# Sheet1.net
KiCad netlist of a schematic drawn in Altium Designer
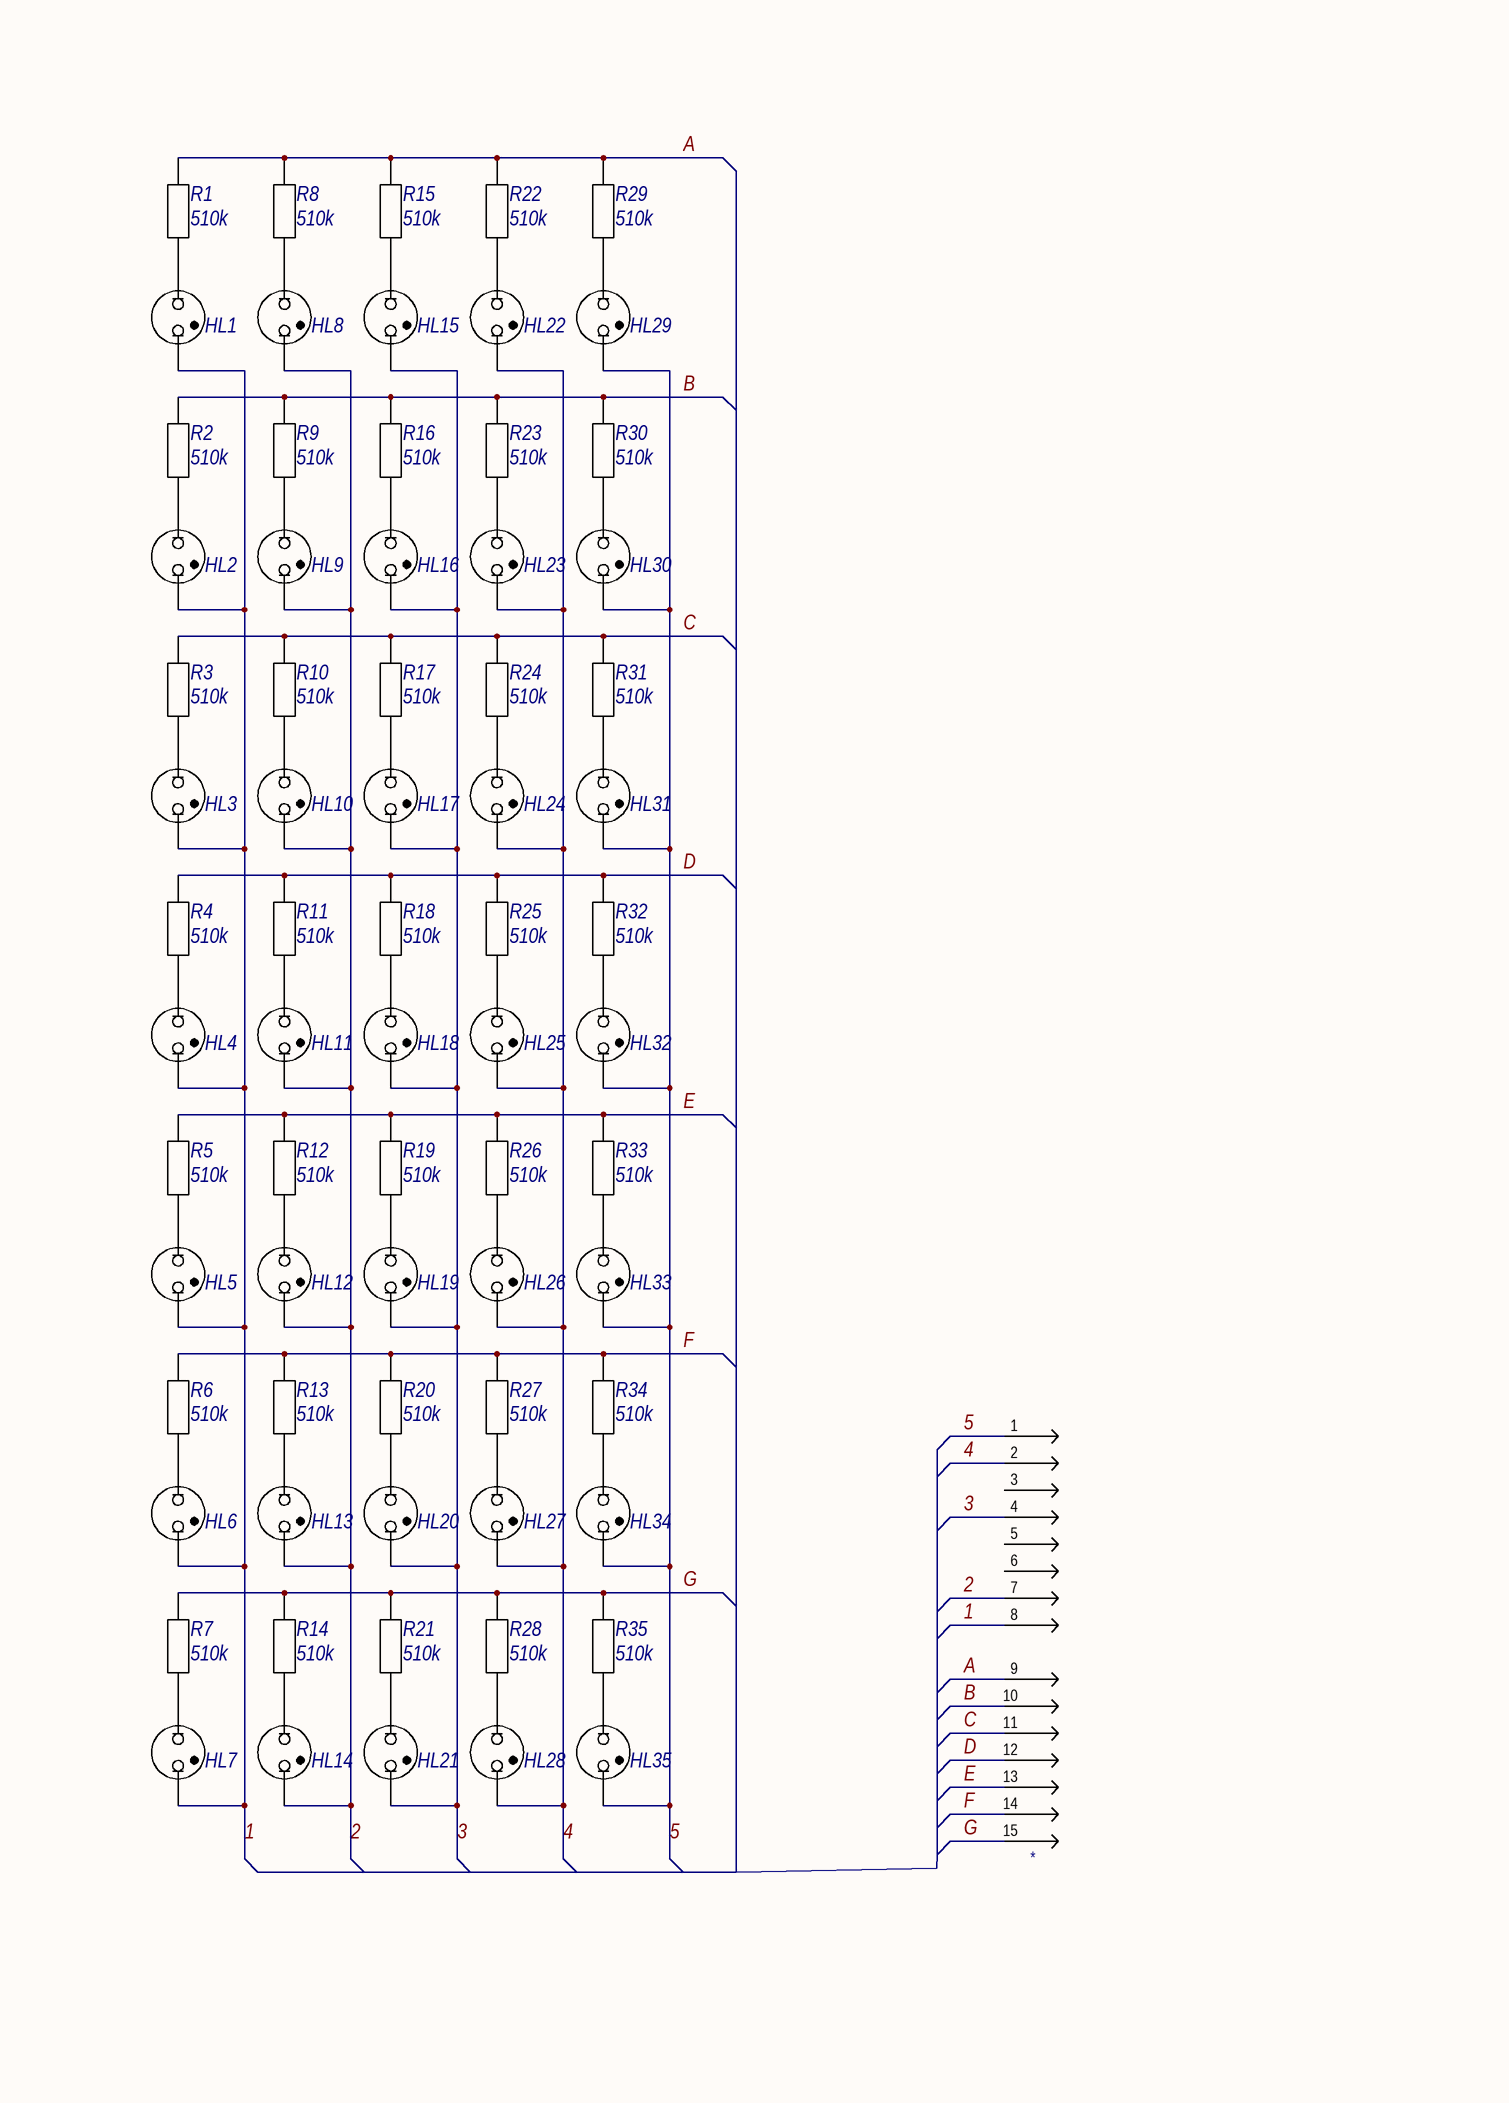
[diagram p0: Sheet1.SchDoc]

(export (version "E")
  (design (tool "Eeschema 10.0.6"))
  (components
    (comp (ref "*")
      (value "Component_1")
      (footprint "DB-15 on PCB")
      (libsource (lib "Schlib1") (part "Component_1"))
    )
    (comp (ref "HL1")
      (value "ne-2")
      (footprint "ne2-4x10")
      (description "Neon Bulb Indicator Lamps 4mm Red")
      (libsource (lib "Schlib1") (part "ne-2"))
    )
    (comp (ref "HL2")
      (value "ne-2")
      (footprint "ne2-4x10")
      (description "Neon Bulb Indicator Lamps 4mm Red")
      (libsource (lib "Schlib1") (part "ne-2"))
    )
    (comp (ref "HL3")
      (value "ne-2")
      (footprint "ne2-4x10")
      (description "Neon Bulb Indicator Lamps 4mm Red")
      (libsource (lib "Schlib1") (part "ne-2"))
    )
    (comp (ref "HL4")
      (value "ne-2")
      (footprint "ne2-4x10")
      (description "Neon Bulb Indicator Lamps 4mm Red")
      (libsource (lib "Schlib1") (part "ne-2"))
    )
    (comp (ref "HL5")
      (value "ne-2")
      (footprint "ne2-4x10")
      (description "Neon Bulb Indicator Lamps 4mm Red")
      (libsource (lib "Schlib1") (part "ne-2"))
    )
    (comp (ref "HL6")
      (value "ne-2")
      (footprint "ne2-4x10")
      (description "Neon Bulb Indicator Lamps 4mm Red")
      (libsource (lib "Schlib1") (part "ne-2"))
    )
    (comp (ref "HL7")
      (value "ne-2")
      (footprint "ne2-4x10")
      (description "Neon Bulb Indicator Lamps 4mm Red")
      (libsource (lib "Schlib1") (part "ne-2"))
    )
    (comp (ref "HL8")
      (value "ne-2")
      (footprint "ne2-4x10")
      (description "Neon Bulb Indicator Lamps 4mm Red")
      (libsource (lib "Schlib1") (part "ne-2"))
    )
    (comp (ref "HL9")
      (value "ne-2")
      (footprint "ne2-4x10")
      (description "Neon Bulb Indicator Lamps 4mm Red")
      (libsource (lib "Schlib1") (part "ne-2"))
    )
    (comp (ref "HL10")
      (value "ne-2")
      (footprint "ne2-4x10")
      (description "Neon Bulb Indicator Lamps 4mm Red")
      (libsource (lib "Schlib1") (part "ne-2"))
    )
    (comp (ref "HL11")
      (value "ne-2")
      (footprint "ne2-4x10")
      (description "Neon Bulb Indicator Lamps 4mm Red")
      (libsource (lib "Schlib1") (part "ne-2"))
    )
    (comp (ref "HL12")
      (value "ne-2")
      (footprint "ne2-4x10")
      (description "Neon Bulb Indicator Lamps 4mm Red")
      (libsource (lib "Schlib1") (part "ne-2"))
    )
    (comp (ref "HL13")
      (value "ne-2")
      (footprint "ne2-4x10")
      (description "Neon Bulb Indicator Lamps 4mm Red")
      (libsource (lib "Schlib1") (part "ne-2"))
    )
    (comp (ref "HL14")
      (value "ne-2")
      (footprint "ne2-4x10")
      (description "Neon Bulb Indicator Lamps 4mm Red")
      (libsource (lib "Schlib1") (part "ne-2"))
    )
    (comp (ref "HL15")
      (value "ne-2")
      (footprint "ne2-4x10")
      (description "Neon Bulb Indicator Lamps 4mm Red")
      (libsource (lib "Schlib1") (part "ne-2"))
    )
    (comp (ref "HL16")
      (value "ne-2")
      (footprint "ne2-4x10")
      (description "Neon Bulb Indicator Lamps 4mm Red")
      (libsource (lib "Schlib1") (part "ne-2"))
    )
    (comp (ref "HL17")
      (value "ne-2")
      (footprint "ne2-4x10")
      (description "Neon Bulb Indicator Lamps 4mm Red")
      (libsource (lib "Schlib1") (part "ne-2"))
    )
    (comp (ref "HL18")
      (value "ne-2")
      (footprint "ne2-4x10")
      (description "Neon Bulb Indicator Lamps 4mm Red")
      (libsource (lib "Schlib1") (part "ne-2"))
    )
    (comp (ref "HL19")
      (value "ne-2")
      (footprint "ne2-4x10")
      (description "Neon Bulb Indicator Lamps 4mm Red")
      (libsource (lib "Schlib1") (part "ne-2"))
    )
    (comp (ref "HL20")
      (value "ne-2")
      (footprint "ne2-4x10")
      (description "Neon Bulb Indicator Lamps 4mm Red")
      (libsource (lib "Schlib1") (part "ne-2"))
    )
    (comp (ref "HL21")
      (value "ne-2")
      (footprint "ne2-4x10")
      (description "Neon Bulb Indicator Lamps 4mm Red")
      (libsource (lib "Schlib1") (part "ne-2"))
    )
    (comp (ref "HL22")
      (value "ne-2")
      (footprint "ne2-4x10")
      (description "Neon Bulb Indicator Lamps 4mm Red")
      (libsource (lib "Schlib1") (part "ne-2"))
    )
    (comp (ref "HL23")
      (value "ne-2")
      (footprint "ne2-4x10")
      (description "Neon Bulb Indicator Lamps 4mm Red")
      (libsource (lib "Schlib1") (part "ne-2"))
    )
    (comp (ref "HL24")
      (value "ne-2")
      (footprint "ne2-4x10")
      (description "Neon Bulb Indicator Lamps 4mm Red")
      (libsource (lib "Schlib1") (part "ne-2"))
    )
    (comp (ref "HL25")
      (value "ne-2")
      (footprint "ne2-4x10")
      (description "Neon Bulb Indicator Lamps 4mm Red")
      (libsource (lib "Schlib1") (part "ne-2"))
    )
    (comp (ref "HL26")
      (value "ne-2")
      (footprint "ne2-4x10")
      (description "Neon Bulb Indicator Lamps 4mm Red")
      (libsource (lib "Schlib1") (part "ne-2"))
    )
    (comp (ref "HL27")
      (value "ne-2")
      (footprint "ne2-4x10")
      (description "Neon Bulb Indicator Lamps 4mm Red")
      (libsource (lib "Schlib1") (part "ne-2"))
    )
    (comp (ref "HL28")
      (value "ne-2")
      (footprint "ne2-4x10")
      (description "Neon Bulb Indicator Lamps 4mm Red")
      (libsource (lib "Schlib1") (part "ne-2"))
    )
    (comp (ref "HL29")
      (value "ne-2")
      (footprint "ne2-4x10")
      (description "Neon Bulb Indicator Lamps 4mm Red")
      (libsource (lib "Schlib1") (part "ne-2"))
    )
    (comp (ref "HL30")
      (value "ne-2")
      (footprint "ne2-4x10")
      (description "Neon Bulb Indicator Lamps 4mm Red")
      (libsource (lib "Schlib1") (part "ne-2"))
    )
    (comp (ref "HL31")
      (value "ne-2")
      (footprint "ne2-4x10")
      (description "Neon Bulb Indicator Lamps 4mm Red")
      (libsource (lib "Schlib1") (part "ne-2"))
    )
    (comp (ref "HL32")
      (value "ne-2")
      (footprint "ne2-4x10")
      (description "Neon Bulb Indicator Lamps 4mm Red")
      (libsource (lib "Schlib1") (part "ne-2"))
    )
    (comp (ref "HL33")
      (value "ne-2")
      (footprint "ne2-4x10")
      (description "Neon Bulb Indicator Lamps 4mm Red")
      (libsource (lib "Schlib1") (part "ne-2"))
    )
    (comp (ref "HL34")
      (value "ne-2")
      (footprint "ne2-4x10")
      (description "Neon Bulb Indicator Lamps 4mm Red")
      (libsource (lib "Schlib1") (part "ne-2"))
    )
    (comp (ref "HL35")
      (value "ne-2")
      (footprint "ne2-4x10")
      (description "Neon Bulb Indicator Lamps 4mm Red")
      (libsource (lib "Schlib1") (part "ne-2"))
    )
    (comp (ref "R1")
      (value "R-1206 0,25 Вт 510kОм Yageo")
      (footprint "R1206")
      (fields
        (field (name "POWER") "0,25 Вт")
        (field (name "MANUFACTURER") "Yageo")
        (field (name "TOLERANCE") "5%")
        (field (name "RESISTANCE") "510k")
      )
      (libsource (lib "Schlib1") (part "R1206"))
    )
    (comp (ref "R2")
      (value "R-1206 0,25 Вт 510kОм Yageo")
      (footprint "R1206")
      (fields
        (field (name "POWER") "0,25 Вт")
        (field (name "MANUFACTURER") "Yageo")
        (field (name "TOLERANCE") "5%")
        (field (name "RESISTANCE") "510k")
      )
      (libsource (lib "Schlib1") (part "R1206"))
    )
    (comp (ref "R3")
      (value "R-1206 0,25 Вт 510kОм Yageo")
      (footprint "R1206")
      (fields
        (field (name "POWER") "0,25 Вт")
        (field (name "MANUFACTURER") "Yageo")
        (field (name "TOLERANCE") "5%")
        (field (name "RESISTANCE") "510k")
      )
      (libsource (lib "Schlib1") (part "R1206"))
    )
    (comp (ref "R4")
      (value "R-1206 0,25 Вт 510kОм Yageo")
      (footprint "R1206")
      (fields
        (field (name "POWER") "0,25 Вт")
        (field (name "MANUFACTURER") "Yageo")
        (field (name "TOLERANCE") "5%")
        (field (name "RESISTANCE") "510k")
      )
      (libsource (lib "Schlib1") (part "R1206"))
    )
    (comp (ref "R5")
      (value "R-1206 0,25 Вт 510kОм Yageo")
      (footprint "R1206")
      (fields
        (field (name "POWER") "0,25 Вт")
        (field (name "MANUFACTURER") "Yageo")
        (field (name "TOLERANCE") "5%")
        (field (name "RESISTANCE") "510k")
      )
      (libsource (lib "Schlib1") (part "R1206"))
    )
    (comp (ref "R6")
      (value "R-1206 0,25 Вт 510kОм Yageo")
      (footprint "R1206")
      (fields
        (field (name "POWER") "0,25 Вт")
        (field (name "MANUFACTURER") "Yageo")
        (field (name "TOLERANCE") "5%")
        (field (name "RESISTANCE") "510k")
      )
      (libsource (lib "Schlib1") (part "R1206"))
    )
    (comp (ref "R7")
      (value "R-1206 0,25 Вт 510kОм Yageo")
      (footprint "R1206")
      (fields
        (field (name "POWER") "0,25 Вт")
        (field (name "MANUFACTURER") "Yageo")
        (field (name "TOLERANCE") "5%")
        (field (name "RESISTANCE") "510k")
      )
      (libsource (lib "Schlib1") (part "R1206"))
    )
    (comp (ref "R8")
      (value "R-1206 0,25 Вт 510kОм Yageo")
      (footprint "R1206")
      (fields
        (field (name "POWER") "0,25 Вт")
        (field (name "MANUFACTURER") "Yageo")
        (field (name "TOLERANCE") "5%")
        (field (name "RESISTANCE") "510k")
      )
      (libsource (lib "Schlib1") (part "R1206"))
    )
    (comp (ref "R9")
      (value "R-1206 0,25 Вт 510kОм Yageo")
      (footprint "R1206")
      (fields
        (field (name "POWER") "0,25 Вт")
        (field (name "MANUFACTURER") "Yageo")
        (field (name "TOLERANCE") "5%")
        (field (name "RESISTANCE") "510k")
      )
      (libsource (lib "Schlib1") (part "R1206"))
    )
    (comp (ref "R10")
      (value "R-1206 0,25 Вт 510kОм Yageo")
      (footprint "R1206")
      (fields
        (field (name "POWER") "0,25 Вт")
        (field (name "MANUFACTURER") "Yageo")
        (field (name "TOLERANCE") "5%")
        (field (name "RESISTANCE") "510k")
      )
      (libsource (lib "Schlib1") (part "R1206"))
    )
    (comp (ref "R11")
      (value "R-1206 0,25 Вт 510kОм Yageo")
      (footprint "R1206")
      (fields
        (field (name "POWER") "0,25 Вт")
        (field (name "MANUFACTURER") "Yageo")
        (field (name "TOLERANCE") "5%")
        (field (name "RESISTANCE") "510k")
      )
      (libsource (lib "Schlib1") (part "R1206"))
    )
    (comp (ref "R12")
      (value "R-1206 0,25 Вт 510kОм Yageo")
      (footprint "R1206")
      (fields
        (field (name "POWER") "0,25 Вт")
        (field (name "MANUFACTURER") "Yageo")
        (field (name "TOLERANCE") "5%")
        (field (name "RESISTANCE") "510k")
      )
      (libsource (lib "Schlib1") (part "R1206"))
    )
    (comp (ref "R13")
      (value "R-1206 0,25 Вт 510kОм Yageo")
      (footprint "R1206")
      (fields
        (field (name "POWER") "0,25 Вт")
        (field (name "MANUFACTURER") "Yageo")
        (field (name "TOLERANCE") "5%")
        (field (name "RESISTANCE") "510k")
      )
      (libsource (lib "Schlib1") (part "R1206"))
    )
    (comp (ref "R14")
      (value "R-1206 0,25 Вт 510kОм Yageo")
      (footprint "R1206")
      (fields
        (field (name "POWER") "0,25 Вт")
        (field (name "MANUFACTURER") "Yageo")
        (field (name "TOLERANCE") "5%")
        (field (name "RESISTANCE") "510k")
      )
      (libsource (lib "Schlib1") (part "R1206"))
    )
    (comp (ref "R15")
      (value "R-1206 0,25 Вт 510kОм Yageo")
      (footprint "R1206")
      (fields
        (field (name "POWER") "0,25 Вт")
        (field (name "MANUFACTURER") "Yageo")
        (field (name "TOLERANCE") "5%")
        (field (name "RESISTANCE") "510k")
      )
      (libsource (lib "Schlib1") (part "R1206"))
    )
    (comp (ref "R16")
      (value "R-1206 0,25 Вт 510kОм Yageo")
      (footprint "R1206")
      (fields
        (field (name "POWER") "0,25 Вт")
        (field (name "MANUFACTURER") "Yageo")
        (field (name "TOLERANCE") "5%")
        (field (name "RESISTANCE") "510k")
      )
      (libsource (lib "Schlib1") (part "R1206"))
    )
    (comp (ref "R17")
      (value "R-1206 0,25 Вт 510kОм Yageo")
      (footprint "R1206")
      (fields
        (field (name "POWER") "0,25 Вт")
        (field (name "MANUFACTURER") "Yageo")
        (field (name "TOLERANCE") "5%")
        (field (name "RESISTANCE") "510k")
      )
      (libsource (lib "Schlib1") (part "R1206"))
    )
    (comp (ref "R18")
      (value "R-1206 0,25 Вт 510kОм Yageo")
      (footprint "R1206")
      (fields
        (field (name "POWER") "0,25 Вт")
        (field (name "MANUFACTURER") "Yageo")
        (field (name "TOLERANCE") "5%")
        (field (name "RESISTANCE") "510k")
      )
      (libsource (lib "Schlib1") (part "R1206"))
    )
    (comp (ref "R19")
      (value "R-1206 0,25 Вт 510kОм Yageo")
      (footprint "R1206")
      (fields
        (field (name "POWER") "0,25 Вт")
        (field (name "MANUFACTURER") "Yageo")
        (field (name "TOLERANCE") "5%")
        (field (name "RESISTANCE") "510k")
      )
      (libsource (lib "Schlib1") (part "R1206"))
    )
    (comp (ref "R20")
      (value "R-1206 0,25 Вт 510kОм Yageo")
      (footprint "R1206")
      (fields
        (field (name "POWER") "0,25 Вт")
        (field (name "MANUFACTURER") "Yageo")
        (field (name "TOLERANCE") "5%")
        (field (name "RESISTANCE") "510k")
      )
      (libsource (lib "Schlib1") (part "R1206"))
    )
    (comp (ref "R21")
      (value "R-1206 0,25 Вт 510kОм Yageo")
      (footprint "R1206")
      (fields
        (field (name "POWER") "0,25 Вт")
        (field (name "MANUFACTURER") "Yageo")
        (field (name "TOLERANCE") "5%")
        (field (name "RESISTANCE") "510k")
      )
      (libsource (lib "Schlib1") (part "R1206"))
    )
    (comp (ref "R22")
      (value "R-1206 0,25 Вт 510kОм Yageo")
      (footprint "R1206")
      (fields
        (field (name "POWER") "0,25 Вт")
        (field (name "MANUFACTURER") "Yageo")
        (field (name "TOLERANCE") "5%")
        (field (name "RESISTANCE") "510k")
      )
      (libsource (lib "Schlib1") (part "R1206"))
    )
    (comp (ref "R23")
      (value "R-1206 0,25 Вт 510kОм Yageo")
      (footprint "R1206")
      (fields
        (field (name "POWER") "0,25 Вт")
        (field (name "MANUFACTURER") "Yageo")
        (field (name "TOLERANCE") "5%")
        (field (name "RESISTANCE") "510k")
      )
      (libsource (lib "Schlib1") (part "R1206"))
    )
    (comp (ref "R24")
      (value "R-1206 0,25 Вт 510kОм Yageo")
      (footprint "R1206")
      (fields
        (field (name "POWER") "0,25 Вт")
        (field (name "MANUFACTURER") "Yageo")
        (field (name "TOLERANCE") "5%")
        (field (name "RESISTANCE") "510k")
      )
      (libsource (lib "Schlib1") (part "R1206"))
    )
    (comp (ref "R25")
      (value "R-1206 0,25 Вт 510kОм Yageo")
      (footprint "R1206")
      (fields
        (field (name "POWER") "0,25 Вт")
        (field (name "MANUFACTURER") "Yageo")
        (field (name "TOLERANCE") "5%")
        (field (name "RESISTANCE") "510k")
      )
      (libsource (lib "Schlib1") (part "R1206"))
    )
    (comp (ref "R26")
      (value "R-1206 0,25 Вт 510kОм Yageo")
      (footprint "R1206")
      (fields
        (field (name "POWER") "0,25 Вт")
        (field (name "MANUFACTURER") "Yageo")
        (field (name "TOLERANCE") "5%")
        (field (name "RESISTANCE") "510k")
      )
      (libsource (lib "Schlib1") (part "R1206"))
    )
    (comp (ref "R27")
      (value "R-1206 0,25 Вт 510kОм Yageo")
      (footprint "R1206")
      (fields
        (field (name "POWER") "0,25 Вт")
        (field (name "MANUFACTURER") "Yageo")
        (field (name "TOLERANCE") "5%")
        (field (name "RESISTANCE") "510k")
      )
      (libsource (lib "Schlib1") (part "R1206"))
    )
    (comp (ref "R28")
      (value "R-1206 0,25 Вт 510kОм Yageo")
      (footprint "R1206")
      (fields
        (field (name "POWER") "0,25 Вт")
        (field (name "MANUFACTURER") "Yageo")
        (field (name "TOLERANCE") "5%")
        (field (name "RESISTANCE") "510k")
      )
      (libsource (lib "Schlib1") (part "R1206"))
    )
    (comp (ref "R29")
      (value "R-1206 0,25 Вт 510kОм Yageo")
      (footprint "R1206")
      (fields
        (field (name "POWER") "0,25 Вт")
        (field (name "MANUFACTURER") "Yageo")
        (field (name "TOLERANCE") "5%")
        (field (name "RESISTANCE") "510k")
      )
      (libsource (lib "Schlib1") (part "R1206"))
    )
    (comp (ref "R30")
      (value "R-1206 0,25 Вт 510kОм Yageo")
      (footprint "R1206")
      (fields
        (field (name "POWER") "0,25 Вт")
        (field (name "MANUFACTURER") "Yageo")
        (field (name "TOLERANCE") "5%")
        (field (name "RESISTANCE") "510k")
      )
      (libsource (lib "Schlib1") (part "R1206"))
    )
    (comp (ref "R31")
      (value "R-1206 0,25 Вт 510kОм Yageo")
      (footprint "R1206")
      (fields
        (field (name "POWER") "0,25 Вт")
        (field (name "MANUFACTURER") "Yageo")
        (field (name "TOLERANCE") "5%")
        (field (name "RESISTANCE") "510k")
      )
      (libsource (lib "Schlib1") (part "R1206"))
    )
    (comp (ref "R32")
      (value "R-1206 0,25 Вт 510kОм Yageo")
      (footprint "R1206")
      (fields
        (field (name "POWER") "0,25 Вт")
        (field (name "MANUFACTURER") "Yageo")
        (field (name "TOLERANCE") "5%")
        (field (name "RESISTANCE") "510k")
      )
      (libsource (lib "Schlib1") (part "R1206"))
    )
    (comp (ref "R33")
      (value "R-1206 0,25 Вт 510kОм Yageo")
      (footprint "R1206")
      (fields
        (field (name "POWER") "0,25 Вт")
        (field (name "MANUFACTURER") "Yageo")
        (field (name "TOLERANCE") "5%")
        (field (name "RESISTANCE") "510k")
      )
      (libsource (lib "Schlib1") (part "R1206"))
    )
    (comp (ref "R34")
      (value "R-1206 0,25 Вт 510kОм Yageo")
      (footprint "R1206")
      (fields
        (field (name "POWER") "0,25 Вт")
        (field (name "MANUFACTURER") "Yageo")
        (field (name "TOLERANCE") "5%")
        (field (name "RESISTANCE") "510k")
      )
      (libsource (lib "Schlib1") (part "R1206"))
    )
    (comp (ref "R35")
      (value "R-1206 0,25 Вт 510kОм Yageo")
      (footprint "R1206")
      (fields
        (field (name "POWER") "0,25 Вт")
        (field (name "MANUFACTURER") "Yageo")
        (field (name "TOLERANCE") "5%")
        (field (name "RESISTANCE") "510k")
      )
      (libsource (lib "Schlib1") (part "R1206"))
    )
  )
  (nets
    (net (code "1") (name "/1") (class "Default")
      (node (ref "*") (pin "8") (pinfunction "8_8") (pintype "passive"))
      (node (ref "HL1") (pin "2") (pinfunction "A_2") (pintype "passive"))
      (node (ref "HL2") (pin "2") (pinfunction "A_2") (pintype "passive"))
      (node (ref "HL3") (pin "2") (pinfunction "A_2") (pintype "passive"))
      (node (ref "HL4") (pin "2") (pinfunction "A_2") (pintype "passive"))
      (node (ref "HL5") (pin "2") (pinfunction "A_2") (pintype "passive"))
      (node (ref "HL6") (pin "2") (pinfunction "A_2") (pintype "passive"))
      (node (ref "HL7") (pin "2") (pinfunction "A_2") (pintype "passive"))
    )
    (net (code "2") (name "/2") (class "Default")
      (node (ref "*") (pin "7") (pinfunction "7_7") (pintype "passive"))
      (node (ref "HL10") (pin "2") (pinfunction "A_2") (pintype "passive"))
      (node (ref "HL11") (pin "2") (pinfunction "A_2") (pintype "passive"))
      (node (ref "HL12") (pin "2") (pinfunction "A_2") (pintype "passive"))
      (node (ref "HL13") (pin "2") (pinfunction "A_2") (pintype "passive"))
      (node (ref "HL14") (pin "2") (pinfunction "A_2") (pintype "passive"))
      (node (ref "HL8") (pin "2") (pinfunction "A_2") (pintype "passive"))
      (node (ref "HL9") (pin "2") (pinfunction "A_2") (pintype "passive"))
    )
    (net (code "3") (name "/3") (class "Default")
      (node (ref "*") (pin "4") (pinfunction "4_4") (pintype "passive"))
      (node (ref "HL15") (pin "2") (pinfunction "A_2") (pintype "passive"))
      (node (ref "HL16") (pin "2") (pinfunction "A_2") (pintype "passive"))
      (node (ref "HL17") (pin "2") (pinfunction "A_2") (pintype "passive"))
      (node (ref "HL18") (pin "2") (pinfunction "A_2") (pintype "passive"))
      (node (ref "HL19") (pin "2") (pinfunction "A_2") (pintype "passive"))
      (node (ref "HL20") (pin "2") (pinfunction "A_2") (pintype "passive"))
      (node (ref "HL21") (pin "2") (pinfunction "A_2") (pintype "passive"))
    )
    (net (code "4") (name "/4") (class "Default")
      (node (ref "*") (pin "2") (pinfunction "2_2") (pintype "passive"))
      (node (ref "HL22") (pin "2") (pinfunction "A_2") (pintype "passive"))
      (node (ref "HL23") (pin "2") (pinfunction "A_2") (pintype "passive"))
      (node (ref "HL24") (pin "2") (pinfunction "A_2") (pintype "passive"))
      (node (ref "HL25") (pin "2") (pinfunction "A_2") (pintype "passive"))
      (node (ref "HL26") (pin "2") (pinfunction "A_2") (pintype "passive"))
      (node (ref "HL27") (pin "2") (pinfunction "A_2") (pintype "passive"))
      (node (ref "HL28") (pin "2") (pinfunction "A_2") (pintype "passive"))
    )
    (net (code "5") (name "/5") (class "Default")
      (node (ref "*") (pin "1") (pinfunction "C4_1") (pintype "passive"))
      (node (ref "HL29") (pin "2") (pinfunction "A_2") (pintype "passive"))
      (node (ref "HL30") (pin "2") (pinfunction "A_2") (pintype "passive"))
      (node (ref "HL31") (pin "2") (pinfunction "A_2") (pintype "passive"))
      (node (ref "HL32") (pin "2") (pinfunction "A_2") (pintype "passive"))
      (node (ref "HL33") (pin "2") (pinfunction "A_2") (pintype "passive"))
      (node (ref "HL34") (pin "2") (pinfunction "A_2") (pintype "passive"))
      (node (ref "HL35") (pin "2") (pinfunction "A_2") (pintype "passive"))
    )
    (net (code "6") (name "/A") (class "Default")
      (node (ref "*") (pin "9") (pinfunction "9_9") (pintype "passive"))
      (node (ref "R1") (pin "2") (pintype "power_in"))
      (node (ref "R15") (pin "2") (pintype "power_in"))
      (node (ref "R22") (pin "2") (pintype "power_in"))
      (node (ref "R29") (pin "2") (pintype "power_in"))
      (node (ref "R8") (pin "2") (pintype "power_in"))
    )
    (net (code "7") (name "/B") (class "Default")
      (node (ref "*") (pin "10") (pinfunction "10_10") (pintype "passive"))
      (node (ref "R16") (pin "2") (pintype "power_in"))
      (node (ref "R2") (pin "2") (pintype "power_in"))
      (node (ref "R23") (pin "2") (pintype "power_in"))
      (node (ref "R30") (pin "2") (pintype "power_in"))
      (node (ref "R9") (pin "2") (pintype "power_in"))
    )
    (net (code "8") (name "/C") (class "Default")
      (node (ref "*") (pin "11") (pinfunction "11_11") (pintype "passive"))
      (node (ref "R10") (pin "2") (pintype "power_in"))
      (node (ref "R17") (pin "2") (pintype "power_in"))
      (node (ref "R24") (pin "2") (pintype "power_in"))
      (node (ref "R3") (pin "2") (pintype "power_in"))
      (node (ref "R31") (pin "2") (pintype "power_in"))
    )
    (net (code "9") (name "/D") (class "Default")
      (node (ref "*") (pin "12") (pinfunction "12_12") (pintype "passive"))
      (node (ref "R11") (pin "2") (pintype "power_in"))
      (node (ref "R18") (pin "2") (pintype "power_in"))
      (node (ref "R25") (pin "2") (pintype "power_in"))
      (node (ref "R32") (pin "2") (pintype "power_in"))
      (node (ref "R4") (pin "2") (pintype "power_in"))
    )
    (net (code "10") (name "/E") (class "Default")
      (node (ref "*") (pin "13") (pinfunction "13_13") (pintype "passive"))
      (node (ref "R12") (pin "2") (pintype "power_in"))
      (node (ref "R19") (pin "2") (pintype "power_in"))
      (node (ref "R26") (pin "2") (pintype "power_in"))
      (node (ref "R33") (pin "2") (pintype "power_in"))
      (node (ref "R5") (pin "2") (pintype "power_in"))
    )
    (net (code "11") (name "/F") (class "Default")
      (node (ref "*") (pin "14") (pinfunction "14_14") (pintype "passive"))
      (node (ref "R13") (pin "2") (pintype "power_in"))
      (node (ref "R20") (pin "2") (pintype "power_in"))
      (node (ref "R27") (pin "2") (pintype "power_in"))
      (node (ref "R34") (pin "2") (pintype "power_in"))
      (node (ref "R6") (pin "2") (pintype "power_in"))
    )
    (net (code "12") (name "/G") (class "Default")
      (node (ref "*") (pin "15") (pinfunction "15_15") (pintype "passive"))
      (node (ref "R14") (pin "2") (pintype "power_in"))
      (node (ref "R21") (pin "2") (pintype "power_in"))
      (node (ref "R28") (pin "2") (pintype "power_in"))
      (node (ref "R35") (pin "2") (pintype "power_in"))
      (node (ref "R7") (pin "2") (pintype "power_in"))
    )
    (net (code "13") (name "Net-(HL1-K)") (class "Default")
      (node (ref "HL1") (pin "1") (pinfunction "K_1") (pintype "passive"))
      (node (ref "R1") (pin "1") (pintype "power_in"))
    )
    (net (code "14") (name "Net-(HL2-K)") (class "Default")
      (node (ref "HL2") (pin "1") (pinfunction "K_1") (pintype "passive"))
      (node (ref "R2") (pin "1") (pintype "power_in"))
    )
    (net (code "15") (name "Net-(HL3-K)") (class "Default")
      (node (ref "HL3") (pin "1") (pinfunction "K_1") (pintype "passive"))
      (node (ref "R3") (pin "1") (pintype "power_in"))
    )
    (net (code "16") (name "Net-(HL4-K)") (class "Default")
      (node (ref "HL4") (pin "1") (pinfunction "K_1") (pintype "passive"))
      (node (ref "R4") (pin "1") (pintype "power_in"))
    )
    (net (code "17") (name "Net-(HL5-K)") (class "Default")
      (node (ref "HL5") (pin "1") (pinfunction "K_1") (pintype "passive"))
      (node (ref "R5") (pin "1") (pintype "power_in"))
    )
    (net (code "18") (name "Net-(HL6-K)") (class "Default")
      (node (ref "HL6") (pin "1") (pinfunction "K_1") (pintype "passive"))
      (node (ref "R6") (pin "1") (pintype "power_in"))
    )
    (net (code "19") (name "Net-(HL7-K)") (class "Default")
      (node (ref "HL7") (pin "1") (pinfunction "K_1") (pintype "passive"))
      (node (ref "R7") (pin "1") (pintype "power_in"))
    )
    (net (code "20") (name "Net-(HL8-K)") (class "Default")
      (node (ref "HL8") (pin "1") (pinfunction "K_1") (pintype "passive"))
      (node (ref "R8") (pin "1") (pintype "power_in"))
    )
    (net (code "21") (name "Net-(HL9-K)") (class "Default")
      (node (ref "HL9") (pin "1") (pinfunction "K_1") (pintype "passive"))
      (node (ref "R9") (pin "1") (pintype "power_in"))
    )
    (net (code "22") (name "Net-(HL10-K)") (class "Default")
      (node (ref "HL10") (pin "1") (pinfunction "K_1") (pintype "passive"))
      (node (ref "R10") (pin "1") (pintype "power_in"))
    )
    (net (code "23") (name "Net-(HL11-K)") (class "Default")
      (node (ref "HL11") (pin "1") (pinfunction "K_1") (pintype "passive"))
      (node (ref "R11") (pin "1") (pintype "power_in"))
    )
    (net (code "24") (name "Net-(HL12-K)") (class "Default")
      (node (ref "HL12") (pin "1") (pinfunction "K_1") (pintype "passive"))
      (node (ref "R12") (pin "1") (pintype "power_in"))
    )
    (net (code "25") (name "Net-(HL13-K)") (class "Default")
      (node (ref "HL13") (pin "1") (pinfunction "K_1") (pintype "passive"))
      (node (ref "R13") (pin "1") (pintype "power_in"))
    )
    (net (code "26") (name "Net-(HL14-K)") (class "Default")
      (node (ref "HL14") (pin "1") (pinfunction "K_1") (pintype "passive"))
      (node (ref "R14") (pin "1") (pintype "power_in"))
    )
    (net (code "27") (name "Net-(HL15-K)") (class "Default")
      (node (ref "HL15") (pin "1") (pinfunction "K_1") (pintype "passive"))
      (node (ref "R15") (pin "1") (pintype "power_in"))
    )
    (net (code "28") (name "Net-(HL16-K)") (class "Default")
      (node (ref "HL16") (pin "1") (pinfunction "K_1") (pintype "passive"))
      (node (ref "R16") (pin "1") (pintype "power_in"))
    )
    (net (code "29") (name "Net-(HL17-K)") (class "Default")
      (node (ref "HL17") (pin "1") (pinfunction "K_1") (pintype "passive"))
      (node (ref "R17") (pin "1") (pintype "power_in"))
    )
    (net (code "30") (name "Net-(HL18-K)") (class "Default")
      (node (ref "HL18") (pin "1") (pinfunction "K_1") (pintype "passive"))
      (node (ref "R18") (pin "1") (pintype "power_in"))
    )
    (net (code "31") (name "Net-(HL19-K)") (class "Default")
      (node (ref "HL19") (pin "1") (pinfunction "K_1") (pintype "passive"))
      (node (ref "R19") (pin "1") (pintype "power_in"))
    )
    (net (code "32") (name "Net-(HL20-K)") (class "Default")
      (node (ref "HL20") (pin "1") (pinfunction "K_1") (pintype "passive"))
      (node (ref "R20") (pin "1") (pintype "power_in"))
    )
    (net (code "33") (name "Net-(HL21-K)") (class "Default")
      (node (ref "HL21") (pin "1") (pinfunction "K_1") (pintype "passive"))
      (node (ref "R21") (pin "1") (pintype "power_in"))
    )
    (net (code "34") (name "Net-(HL22-K)") (class "Default")
      (node (ref "HL22") (pin "1") (pinfunction "K_1") (pintype "passive"))
      (node (ref "R22") (pin "1") (pintype "power_in"))
    )
    (net (code "35") (name "Net-(HL23-K)") (class "Default")
      (node (ref "HL23") (pin "1") (pinfunction "K_1") (pintype "passive"))
      (node (ref "R23") (pin "1") (pintype "power_in"))
    )
    (net (code "36") (name "Net-(HL24-K)") (class "Default")
      (node (ref "HL24") (pin "1") (pinfunction "K_1") (pintype "passive"))
      (node (ref "R24") (pin "1") (pintype "power_in"))
    )
    (net (code "37") (name "Net-(HL25-K)") (class "Default")
      (node (ref "HL25") (pin "1") (pinfunction "K_1") (pintype "passive"))
      (node (ref "R25") (pin "1") (pintype "power_in"))
    )
    (net (code "38") (name "Net-(HL26-K)") (class "Default")
      (node (ref "HL26") (pin "1") (pinfunction "K_1") (pintype "passive"))
      (node (ref "R26") (pin "1") (pintype "power_in"))
    )
    (net (code "39") (name "Net-(HL27-K)") (class "Default")
      (node (ref "HL27") (pin "1") (pinfunction "K_1") (pintype "passive"))
      (node (ref "R27") (pin "1") (pintype "power_in"))
    )
    (net (code "40") (name "Net-(HL28-K)") (class "Default")
      (node (ref "HL28") (pin "1") (pinfunction "K_1") (pintype "passive"))
      (node (ref "R28") (pin "1") (pintype "power_in"))
    )
    (net (code "41") (name "Net-(HL29-K)") (class "Default")
      (node (ref "HL29") (pin "1") (pinfunction "K_1") (pintype "passive"))
      (node (ref "R29") (pin "1") (pintype "power_in"))
    )
    (net (code "42") (name "Net-(HL30-K)") (class "Default")
      (node (ref "HL30") (pin "1") (pinfunction "K_1") (pintype "passive"))
      (node (ref "R30") (pin "1") (pintype "power_in"))
    )
    (net (code "43") (name "Net-(HL31-K)") (class "Default")
      (node (ref "HL31") (pin "1") (pinfunction "K_1") (pintype "passive"))
      (node (ref "R31") (pin "1") (pintype "power_in"))
    )
    (net (code "44") (name "Net-(HL32-K)") (class "Default")
      (node (ref "HL32") (pin "1") (pinfunction "K_1") (pintype "passive"))
      (node (ref "R32") (pin "1") (pintype "power_in"))
    )
    (net (code "45") (name "Net-(HL33-K)") (class "Default")
      (node (ref "HL33") (pin "1") (pinfunction "K_1") (pintype "passive"))
      (node (ref "R33") (pin "1") (pintype "power_in"))
    )
    (net (code "46") (name "Net-(HL34-K)") (class "Default")
      (node (ref "HL34") (pin "1") (pinfunction "K_1") (pintype "passive"))
      (node (ref "R34") (pin "1") (pintype "power_in"))
    )
    (net (code "47") (name "Net-(HL35-K)") (class "Default")
      (node (ref "HL35") (pin "1") (pinfunction "K_1") (pintype "passive"))
      (node (ref "R35") (pin "1") (pintype "power_in"))
    )
    (net (code "48") (name "unconnected-(*-Pad3)") (class "Default")
      (node (ref "*") (pin "3") (pinfunction "3_3") (pintype "passive"))
    )
    (net (code "49") (name "unconnected-(*-Pad5)") (class "Default")
      (node (ref "*") (pin "5") (pinfunction "5_5") (pintype "passive"))
    )
    (net (code "50") (name "unconnected-(*-Pad6)") (class "Default")
      (node (ref "*") (pin "6") (pinfunction "6_6") (pintype "passive"))
    )
  )
)
